# VOLTAGE_REGULATOR_AC_TO_12V_DC_PCB_CIRCU.net
KiCad netlist of a schematic drawn in Altium Designer
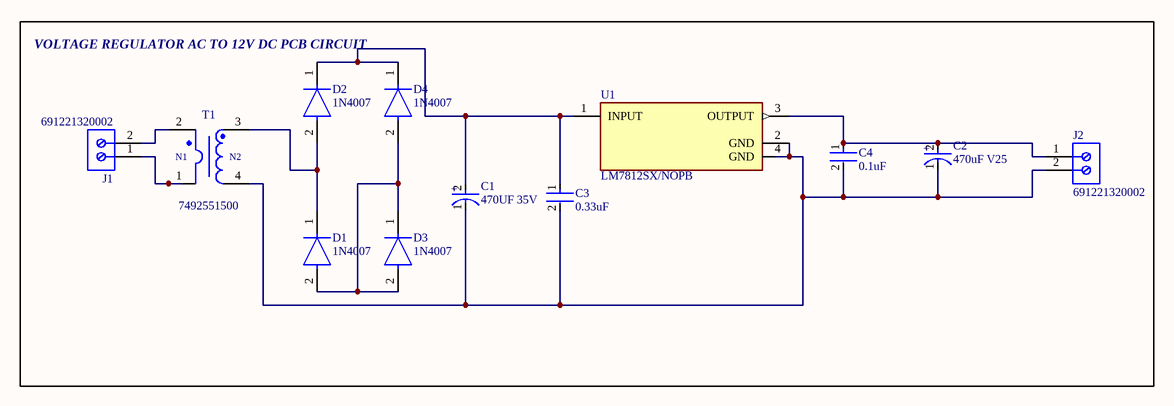
[diagram p0: VOLTAGE REGULATOR AC TO 12V DC PCB CIRCUIT.SchDoc]

(export (version "E")
  (design (tool "Eeschema 10.0.6"))
  (components
    (comp (ref "C1")
      (value "470UF 35V")
      (footprint "FP-FKH13-MFG")
      (description "CAP ALUM 470UF 20% 35V SMD")
      (fields (field (name "TOLERANCE") "20%") (field (name "VOLTAGE") "35V"))
      (libsource (lib "Altium Content Vault") (part "203bc49f2ac43e59fd269a8c329ed05"))
    )
    (comp (ref "C2")
      (value "470uF V25")
      (footprint "FP-477AVG025MFBJ-MFG")
      (fields (field (name "TOLERANCE") "20%"))
      (libsource (lib "Altium Content Vault") (part "a00bbbee19879c290e62620ae7e47b1"))
    )
    (comp (ref "C3")
      (value "0.33uF")
      (footprint "FP-GCJ21B-0_3-IPC_C")
      (description "Multilayer Ceramic Capacitors MLCC - SMD/SMT 0805 0.33uF 10%, 50VDC,  X7R 15%")
      (libsource (lib "Altium Content Vault") (part "02cd4be3c70576c341d710602a673aa"))
    )
    (comp (ref "C4")
      (value "0.1uF")
      (footprint "FP-GCG188-0_2-IPC_A")
      (libsource (lib "Altium Content Vault") (part "02cd4be3c70576c341d710602a673aa"))
    )
    (comp (ref "D1")
      (value "1N4007")
      (footprint "FP-1N4007-MFG")
      (description "Rectifier diode 1000 V 1 A DO-41, ,")
      (fields
        (field (name "MANUFACTURER") "Diotec")
        (field (name "OCTOPART") "https://octopart.com/1n4007-diotec-4040411")
      )
      (libsource (lib "Altium Content Vault") (part "d7152d700b627762746794eb795d46e"))
    )
    (comp (ref "D2")
      (value "1N4007")
      (footprint "FP-1N4007-MFG")
      (description "Rectifier diode 1000 V 1 A DO-41, ,")
      (fields
        (field (name "MANUFACTURER") "Diotec")
        (field (name "OCTOPART") "https://octopart.com/1n4007-diotec-4040411")
      )
      (libsource (lib "Altium Content Vault") (part "d7152d700b627762746794eb795d46e"))
    )
    (comp (ref "D3")
      (value "1N4007")
      (footprint "FP-1N4007-MFG")
      (description "Rectifier diode 1000 V 1 A DO-41, ,")
      (fields
        (field (name "MANUFACTURER") "Diotec")
        (field (name "OCTOPART") "https://octopart.com/1n4007-diotec-4040411")
      )
      (libsource (lib "Altium Content Vault") (part "d7152d700b627762746794eb795d46e"))
    )
    (comp (ref "D4")
      (value "1N4007")
      (footprint "FP-1N4007-MFG")
      (description "Rectifier diode 1000 V 1 A DO-41, ,")
      (fields
        (field (name "MANUFACTURER") "Diotec")
        (field (name "OCTOPART") "https://octopart.com/1n4007-diotec-4040411")
      )
      (libsource (lib "Altium Content Vault") (part "d7152d700b627762746794eb795d46e"))
    )
    (comp (ref "J1")
      (value "691221320002")
      (footprint "691221320002")
      (description "Terminal Block, 3.81MM Pitch, 55DEG, Rising Cage Clamp, 28-16AWG, 2 Pin")
      (libsource (lib "Altium Content Vault") (part "TBL - 1R - 02P - Screw"))
    )
    (comp (ref "J2")
      (value "691221320002")
      (footprint "691221320002")
      (description "Terminal Block, 3.81MM Pitch, 55DEG, Rising Cage Clamp, 28-16AWG, 2 Pin")
      (libsource (lib "Altium Content Vault") (part "TBL - 1R - 02P - Screw"))
    )
    (comp (ref "T1")
      (value "7492551500")
      (footprint "WE-CSTLF_EI187")
      (description "Current Sense Transformer, 3.6H, Th Rohs Compliant: Yes")
      (libsource (lib "Altium Content Vault") (part "WE-CSTLF"))
    )
    (comp (ref "U1")
      (value "LM7812SX/NOPB")
      (footprint "FP-KTT0003B-MFG")
      (description "IC REG LIN 12V 1.5A DDPAK/TO263")
      (libsource (lib "Altium Content Vault") (part "9fcafc0f30dec4b56324498499a9e63"))
    )
  )
  (nets
    (net (code "1") (name "Net-(C1-A)") (class "Default")
      (node (ref "C1") (pin "2") (pinfunction "A_2") (pintype "passive"))
      (node (ref "C3") (pin "1") (pinfunction "1_1") (pintype "passive"))
      (node (ref "D2") (pin "1") (pinfunction "C_1") (pintype "passive"))
      (node (ref "D4") (pin "1") (pinfunction "C_1") (pintype "passive"))
      (node (ref "U1") (pin "1") (pinfunction "INPUT_1") (pintype "power_in"))
    )
    (net (code "2") (name "Net-(C1-C)") (class "Default")
      (node (ref "C1") (pin "1") (pinfunction "C_1") (pintype "passive"))
      (node (ref "C2") (pin "1") (pinfunction "C_1") (pintype "passive"))
      (node (ref "C3") (pin "2") (pinfunction "2_2") (pintype "passive"))
      (node (ref "C4") (pin "2") (pinfunction "2_2") (pintype "passive"))
      (node (ref "J2") (pin "2") (pinfunction "2_2") (pintype "passive"))
      (node (ref "T1") (pin "4") (pinfunction "4_4") (pintype "passive"))
      (node (ref "U1") (pin "2") (pinfunction "GND_2") (pintype "power_in"))
      (node (ref "U1") (pin "4") (pinfunction "GND_4") (pintype "power_in"))
    )
    (net (code "3") (name "Net-(C2-A)") (class "Default")
      (node (ref "C2") (pin "2") (pinfunction "A_2") (pintype "passive"))
      (node (ref "C4") (pin "1") (pinfunction "1_1") (pintype "passive"))
      (node (ref "J2") (pin "1") (pinfunction "1_1") (pintype "passive"))
      (node (ref "U1") (pin "3") (pinfunction "OUTPUT_3") (pintype "output"))
    )
    (net (code "4") (name "Net-(D1-A)") (class "Default")
      (node (ref "D1") (pin "2") (pinfunction "A_2") (pintype "passive"))
      (node (ref "D3") (pin "1") (pinfunction "C_1") (pintype "passive"))
      (node (ref "D3") (pin "2") (pinfunction "A_2") (pintype "passive"))
      (node (ref "D4") (pin "2") (pinfunction "A_2") (pintype "passive"))
    )
    (net (code "5") (name "Net-(D1-C)") (class "Default")
      (node (ref "D1") (pin "1") (pinfunction "C_1") (pintype "passive"))
      (node (ref "D2") (pin "2") (pinfunction "A_2") (pintype "passive"))
      (node (ref "T1") (pin "3") (pinfunction "3_3") (pintype "passive"))
    )
    (net (code "6") (name "Net-(J1-Pad1)") (class "Default")
      (node (ref "J1") (pin "1") (pinfunction "1_1") (pintype "passive"))
      (node (ref "T1") (pin "1") (pinfunction "1_1") (pintype "passive"))
    )
    (net (code "7") (name "Net-(J1-Pad2)") (class "Default")
      (node (ref "J1") (pin "2") (pinfunction "2_2") (pintype "passive"))
      (node (ref "T1") (pin "2") (pinfunction "2_2") (pintype "passive"))
    )
  )
)
